# rfmboard.net
KiCad netlist of a schematic drawn in EAGLE
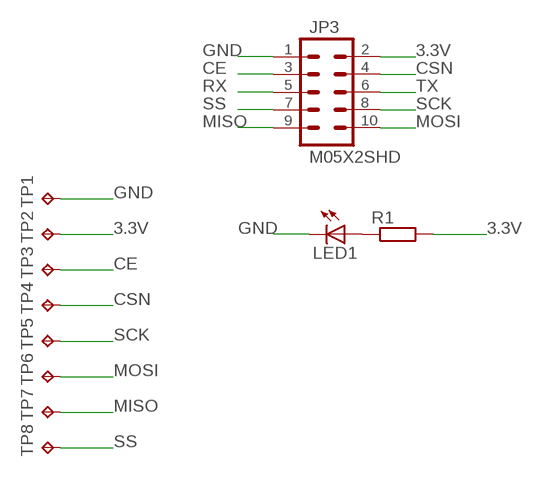
[diagram p0: schematic, sheet 1]

(export (version "E")
  (design (tool "Eeschema 10.0.6"))
  (components
    (comp (ref "JP3")
      (value "M05X2SHD")
      (footprint "eagle-import:2X5-SHROUDED")
      (libsource (lib "eagle-import") (part "M05X2SHD"))
    )
    (comp (ref "LED1")
      (value "LEDSML0805")
      (footprint "eagle-import:SML0805")
      (libsource (lib "eagle-import") (part "LEDSML0805"))
    )
    (comp (ref "R1")
      (value "R-EU_R0805")
      (footprint "eagle-import:R0805")
      (libsource (lib "eagle-import") (part "R-EU_R0805"))
    )
    (comp (ref "TP1")
      (value "TPB1,27")
      (footprint "eagle-import:B1,27")
      (libsource (lib "eagle-import") (part "TPB1,27"))
    )
    (comp (ref "TP2")
      (value "TPB1,27")
      (footprint "eagle-import:B1,27")
      (libsource (lib "eagle-import") (part "TPB1,27"))
    )
    (comp (ref "TP3")
      (value "TPB1,27")
      (footprint "eagle-import:B1,27")
      (libsource (lib "eagle-import") (part "TPB1,27"))
    )
    (comp (ref "TP4")
      (value "TPB1,27")
      (footprint "eagle-import:B1,27")
      (libsource (lib "eagle-import") (part "TPB1,27"))
    )
    (comp (ref "TP5")
      (value "TPB1,27")
      (footprint "eagle-import:B1,27")
      (libsource (lib "eagle-import") (part "TPB1,27"))
    )
    (comp (ref "TP6")
      (value "TPB1,27")
      (footprint "eagle-import:B1,27")
      (libsource (lib "eagle-import") (part "TPB1,27"))
    )
    (comp (ref "TP7")
      (value "TPB1,27")
      (footprint "eagle-import:B1,27")
      (libsource (lib "eagle-import") (part "TPB1,27"))
    )
    (comp (ref "TP8")
      (value "TPB1,27")
      (footprint "eagle-import:B1,27")
      (libsource (lib "eagle-import") (part "TPB1,27"))
    )
  )
  (nets
    (net (code "1") (name "/3.3V") (class "Default")
      (node (ref "JP3") (pin "2") (pinfunction "2_2") (pintype "passive"))
      (node (ref "R1") (pin "2") (pinfunction "2_2") (pintype "passive"))
      (node (ref "TP2") (pin "TP") (pinfunction "TP_TP") (pintype "input"))
    )
    (net (code "2") (name "/CE") (class "Default")
      (node (ref "JP3") (pin "3") (pinfunction "3_3") (pintype "passive"))
      (node (ref "TP3") (pin "TP") (pinfunction "TP_TP") (pintype "input"))
    )
    (net (code "3") (name "/CSN") (class "Default")
      (node (ref "JP3") (pin "4") (pinfunction "4_4") (pintype "passive"))
      (node (ref "TP4") (pin "TP") (pinfunction "TP_TP") (pintype "input"))
    )
    (net (code "4") (name "/GND") (class "Default")
      (node (ref "JP3") (pin "1") (pinfunction "1_1") (pintype "passive"))
      (node (ref "LED1") (pin "C") (pinfunction "C_C") (pintype "passive"))
      (node (ref "TP1") (pin "TP") (pinfunction "TP_TP") (pintype "input"))
    )
    (net (code "5") (name "/MISO") (class "Default")
      (node (ref "JP3") (pin "9") (pinfunction "9_9") (pintype "passive"))
      (node (ref "TP7") (pin "TP") (pinfunction "TP_TP") (pintype "input"))
    )
    (net (code "6") (name "/MOSI") (class "Default")
      (node (ref "JP3") (pin "10") (pinfunction "10_10") (pintype "passive"))
      (node (ref "TP6") (pin "TP") (pinfunction "TP_TP") (pintype "input"))
    )
    (net (code "7") (name "/RX") (class "Default")
      (node (ref "JP3") (pin "5") (pinfunction "5_5") (pintype "passive"))
    )
    (net (code "8") (name "/SCK") (class "Default")
      (node (ref "JP3") (pin "8") (pinfunction "8_8") (pintype "passive"))
      (node (ref "TP5") (pin "TP") (pinfunction "TP_TP") (pintype "input"))
    )
    (net (code "9") (name "/SS") (class "Default")
      (node (ref "JP3") (pin "7") (pinfunction "7_7") (pintype "passive"))
      (node (ref "TP8") (pin "TP") (pinfunction "TP_TP") (pintype "input"))
    )
    (net (code "10") (name "/TX") (class "Default")
      (node (ref "JP3") (pin "6") (pinfunction "6_6") (pintype "passive"))
    )
    (net (code "11") (name "Net-(LED1-PadA)") (class "Default")
      (node (ref "LED1") (pin "A") (pinfunction "A_A") (pintype "passive"))
      (node (ref "R1") (pin "1") (pinfunction "1_1") (pintype "passive"))
    )
  )
)
